# ControlBoard.net
KiCad netlist of a schematic drawn in EAGLE
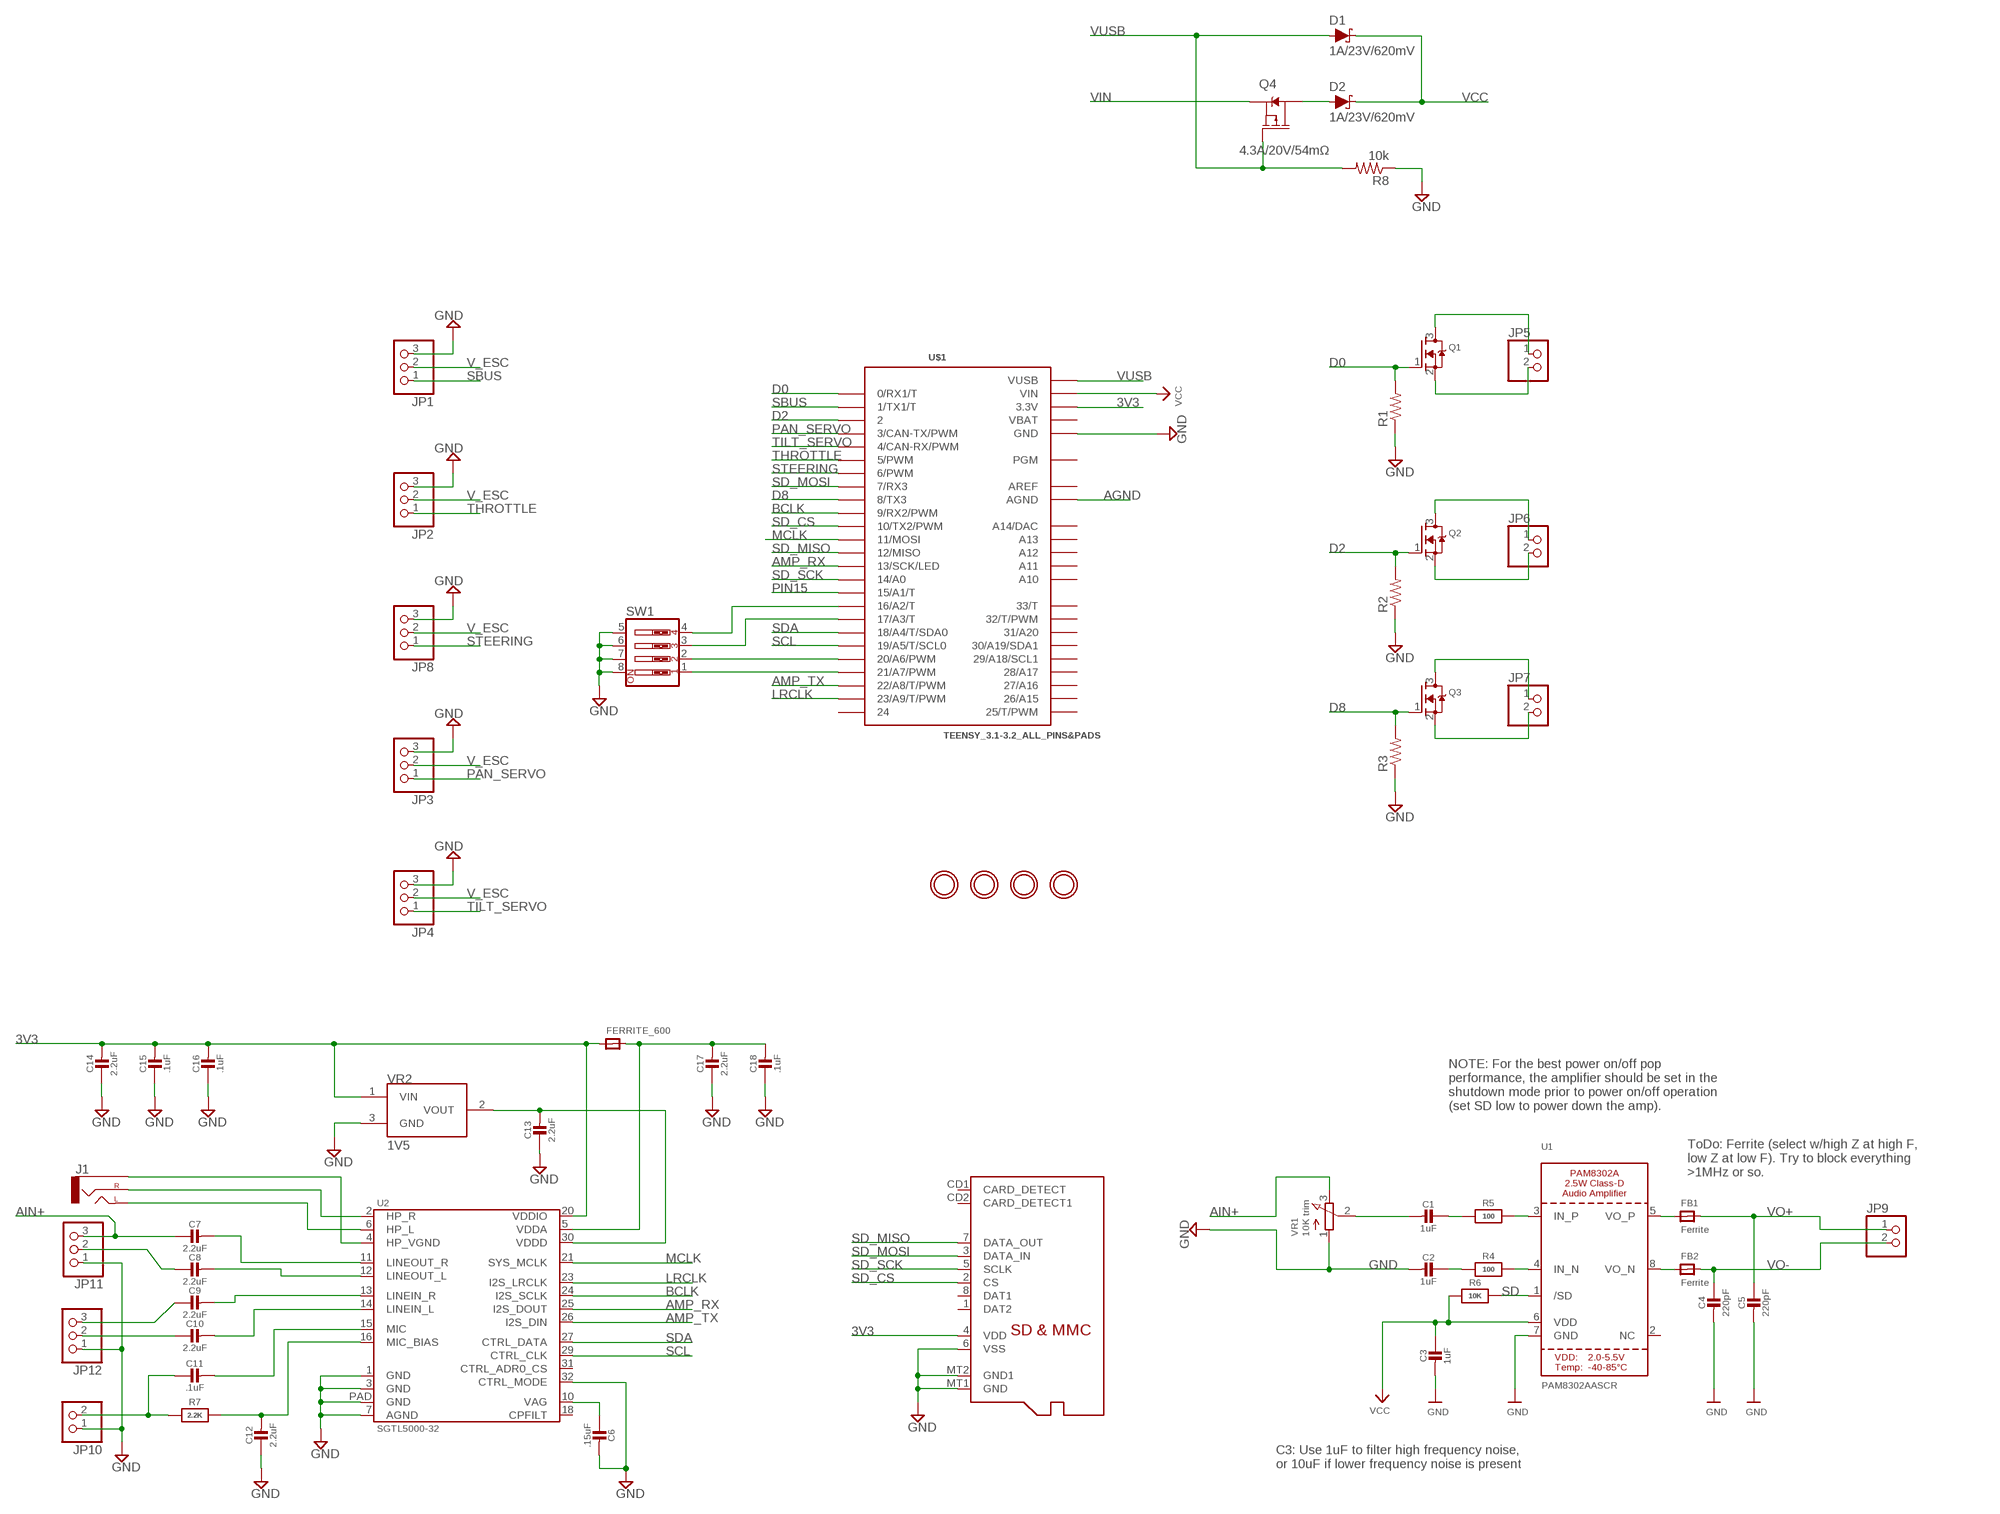
[diagram p0: schematic, sheet 1]

(export (version "E")
  (design (tool "Eeschema 10.0.6"))
  (components
    (comp (ref "C1")
      (value "1uF")
      (footprint "eagle-import:0805-NO")
      (libsource (lib "eagle-import") (part "microbuilder_CAP_CERAMIC0805-NOOUTLINE"))
    )
    (comp (ref "C2")
      (value "1uF")
      (footprint "eagle-import:0805-NO")
      (libsource (lib "eagle-import") (part "microbuilder_CAP_CERAMIC0805-NOOUTLINE"))
    )
    (comp (ref "C3")
      (value "1uF")
      (footprint "eagle-import:0805-NO")
      (libsource (lib "eagle-import") (part "microbuilder_CAP_CERAMIC0805-NOOUTLINE"))
    )
    (comp (ref "C4")
      (value "220pF")
      (footprint "eagle-import:0805-NO")
      (libsource (lib "eagle-import") (part "microbuilder_CAP_CERAMIC0805-NOOUTLINE"))
    )
    (comp (ref "C5")
      (value "220pF")
      (footprint "eagle-import:0805-NO")
      (libsource (lib "eagle-import") (part "microbuilder_CAP_CERAMIC0805-NOOUTLINE"))
    )
    (comp (ref "C6")
      (value ".15uF")
      (footprint "eagle-import:0805-NO")
      (libsource (lib "eagle-import") (part "microbuilder_CAP_CERAMIC0805-NOOUTLINE"))
    )
    (comp (ref "C7")
      (value "2.2uF")
      (footprint "eagle-import:0805-NO")
      (libsource (lib "eagle-import") (part "microbuilder_CAP_CERAMIC0805-NOOUTLINE"))
    )
    (comp (ref "C8")
      (value "2.2uF")
      (footprint "eagle-import:0805-NO")
      (libsource (lib "eagle-import") (part "microbuilder_CAP_CERAMIC0805-NOOUTLINE"))
    )
    (comp (ref "C9")
      (value "2.2uF")
      (footprint "eagle-import:0805-NO")
      (libsource (lib "eagle-import") (part "microbuilder_CAP_CERAMIC0805-NOOUTLINE"))
    )
    (comp (ref "C10")
      (value "2.2uF")
      (footprint "eagle-import:0805-NO")
      (libsource (lib "eagle-import") (part "microbuilder_CAP_CERAMIC0805-NOOUTLINE"))
    )
    (comp (ref "C11")
      (value ".1uF")
      (footprint "eagle-import:0805-NO")
      (libsource (lib "eagle-import") (part "microbuilder_CAP_CERAMIC0805-NOOUTLINE"))
    )
    (comp (ref "C12")
      (value "2.2uF")
      (footprint "eagle-import:0805-NO")
      (libsource (lib "eagle-import") (part "microbuilder_CAP_CERAMIC0805-NOOUTLINE"))
    )
    (comp (ref "C13")
      (value "2.2uF")
      (footprint "eagle-import:0805-NO")
      (libsource (lib "eagle-import") (part "CAP_CERAMIC0805-NOOUTLINE"))
    )
    (comp (ref "C14")
      (value "2.2uF")
      (footprint "eagle-import:0805-NO")
      (libsource (lib "eagle-import") (part "CAP_CERAMIC0805-NOOUTLINE"))
    )
    (comp (ref "C15")
      (value ".1uF")
      (footprint "eagle-import:0805-NO")
      (libsource (lib "eagle-import") (part "CAP_CERAMIC0805-NOOUTLINE"))
    )
    (comp (ref "C16")
      (value ".1uF")
      (footprint "eagle-import:0805-NO")
      (libsource (lib "eagle-import") (part "CAP_CERAMIC0805-NOOUTLINE"))
    )
    (comp (ref "C17")
      (value "2.2uF")
      (footprint "eagle-import:0805-NO")
      (libsource (lib "eagle-import") (part "CAP_CERAMIC0805-NOOUTLINE"))
    )
    (comp (ref "C18")
      (value ".1uF")
      (footprint "eagle-import:0805-NO")
      (libsource (lib "eagle-import") (part "CAP_CERAMIC0805-NOOUTLINE"))
    )
    (comp (ref "D1")
      (value "1A/23V/620mV")
      (footprint "eagle-import:SOD-323")
      (libsource (lib "eagle-import") (part "DIODE-SCHOTTKY-BAT20J"))
    )
    (comp (ref "D2")
      (value "1A/23V/620mV")
      (footprint "eagle-import:SOD-323")
      (libsource (lib "eagle-import") (part "DIODE-SCHOTTKY-BAT20J"))
    )
    (comp (ref "FB1")
      (value "Ferrite")
      (footprint "eagle-import:_0805")
      (libsource (lib "eagle-import") (part "microbuilder_FERRITE_0805"))
    )
    (comp (ref "FB2")
      (value "Ferrite")
      (footprint "eagle-import:_0805")
      (libsource (lib "eagle-import") (part "microbuilder_FERRITE_0805"))
    )
    (comp (ref "FERRITE_600")
      (value "FERRITE0805")
      (footprint "eagle-import:0805")
      (libsource (lib "eagle-import") (part "FERRITE0805"))
    )
    (comp (ref "J1")
      (value "AUDIO_JACK_2.5MM_2.5MM_SMD")
      (footprint "eagle-import:STEREOJACK2.5MM")
      (libsource (lib "eagle-import") (part "AUDIO_JACK_2.5MM_2.5MM_SMD"))
    )
    (comp (ref "JP1")
      (value "PINHD-1X3/90")
      (footprint "eagle-import:1X03_90")
      (libsource (lib "eagle-import") (part "PINHD-1X3/90"))
    )
    (comp (ref "JP2")
      (value "PINHD-1X3/90")
      (footprint "eagle-import:1X03_90")
      (libsource (lib "eagle-import") (part "PINHD-1X3/90"))
    )
    (comp (ref "JP3")
      (value "PINHD-1X3/90")
      (footprint "eagle-import:1X03_90")
      (libsource (lib "eagle-import") (part "PINHD-1X3/90"))
    )
    (comp (ref "JP4")
      (value "PINHD-1X3/90")
      (footprint "eagle-import:1X03_90")
      (libsource (lib "eagle-import") (part "PINHD-1X3/90"))
    )
    (comp (ref "JP5")
      (value "PINHD-1X2")
      (footprint "eagle-import:1X02")
      (libsource (lib "eagle-import") (part "PINHD-1X2"))
    )
    (comp (ref "JP6")
      (value "PINHD-1X2")
      (footprint "eagle-import:1X02")
      (libsource (lib "eagle-import") (part "PINHD-1X2"))
    )
    (comp (ref "JP7")
      (value "PINHD-1X2")
      (footprint "eagle-import:1X02")
      (libsource (lib "eagle-import") (part "PINHD-1X2"))
    )
    (comp (ref "JP8")
      (value "PINHD-1X3/90")
      (footprint "eagle-import:1X03_90")
      (libsource (lib "eagle-import") (part "PINHD-1X3/90"))
    )
    (comp (ref "JP9")
      (value "PINHD-1X2")
      (footprint "eagle-import:1X02")
      (libsource (lib "eagle-import") (part "PINHD-1X2"))
    )
    (comp (ref "JP10")
      (value "PINHD-1X2")
      (footprint "eagle-import:1X02")
      (libsource (lib "eagle-import") (part "PINHD-1X2"))
    )
    (comp (ref "JP11")
      (value "PINHD-1X3/90")
      (footprint "eagle-import:1X03_90")
      (libsource (lib "eagle-import") (part "PINHD-1X3/90"))
    )
    (comp (ref "JP12")
      (value "PINHD-1X3/90")
      (footprint "eagle-import:1X03_90")
      (libsource (lib "eagle-import") (part "PINHD-1X3/90"))
    )
    (comp (ref "Q1")
      (value "MOSFET-NREFLOW")
      (footprint "eagle-import:SOT23")
      (libsource (lib "eagle-import") (part "MOSFET-NREFLOW"))
    )
    (comp (ref "Q2")
      (value "MOSFET-NREFLOW")
      (footprint "eagle-import:SOT23")
      (libsource (lib "eagle-import") (part "MOSFET-NREFLOW"))
    )
    (comp (ref "Q3")
      (value "MOSFET-NREFLOW")
      (footprint "eagle-import:SOT23")
      (libsource (lib "eagle-import") (part "MOSFET-NREFLOW"))
    )
    (comp (ref "Q4")
      (value "4.3A/20V/54mΩ")
      (footprint "eagle-import:SOT23-3")
      (libsource (lib "eagle-import") (part "MOSFET_PCH-IRLML2244"))
    )
    (comp (ref "R1")
      (value "R-US_0207/7")
      (footprint "eagle-import:0207_7")
      (libsource (lib "eagle-import") (part "R-US_0207/7"))
    )
    (comp (ref "R2")
      (value "R-US_0207/7")
      (footprint "eagle-import:0207_7")
      (libsource (lib "eagle-import") (part "R-US_0207/7"))
    )
    (comp (ref "R3")
      (value "R-US_0207/7")
      (footprint "eagle-import:0207_7")
      (libsource (lib "eagle-import") (part "R-US_0207/7"))
    )
    (comp (ref "R4")
      (value "100")
      (footprint "eagle-import:0805-NO")
      (libsource (lib "eagle-import") (part "RESISTOR0805_NOOUTLINE"))
    )
    (comp (ref "R5")
      (value "100")
      (footprint "eagle-import:0805-NO")
      (libsource (lib "eagle-import") (part "RESISTOR0805_NOOUTLINE"))
    )
    (comp (ref "R6")
      (value "10K")
      (footprint "eagle-import:0805-NO")
      (libsource (lib "eagle-import") (part "RESISTOR0805_NOOUTLINE"))
    )
    (comp (ref "R7")
      (value "2.2K")
      (footprint "eagle-import:0805-NO")
      (libsource (lib "eagle-import") (part "RESISTOR0805_NOOUTLINE"))
    )
    (comp (ref "R8")
      (value "10k")
      (footprint "eagle-import:0207_7")
      (libsource (lib "eagle-import") (part "R-US_0207/7"))
    )
    (comp (ref "SW1")
      (value "SW_DIP-4")
      (footprint "eagle-import:EDG-04")
      (libsource (lib "eagle-import") (part "SW_DIP-4"))
    )
    (comp (ref "U$1")
      (value "TEENSY_3.1-3.2_ALL_PINS&PADS")
      (footprint "eagle-import:TEENSY_3.0-3.2_ALL_PINS_&_PADS")
      (libsource (lib "eagle-import") (part "TEENSY_3.1-3.2_ALL_PINS&PADS"))
    )
    (comp (ref "U$4")
      (value "MOUNTINGHOLE2.0")
      (footprint "eagle-import:MOUNTINGHOLE_2.0_PLATED")
      (libsource (lib "eagle-import") (part "MOUNTINGHOLE2.0"))
    )
    (comp (ref "U$5")
      (value "MOUNTINGHOLE2.0")
      (footprint "eagle-import:MOUNTINGHOLE_2.0_PLATED")
      (libsource (lib "eagle-import") (part "MOUNTINGHOLE2.0"))
    )
    (comp (ref "U$6")
      (value "MICROSD")
      (footprint "eagle-import:MICROSD")
      (libsource (lib "eagle-import") (part "MICROSD"))
    )
    (comp (ref "U$10")
      (value "MOUNTINGHOLE2.0")
      (footprint "eagle-import:MOUNTINGHOLE_2.0_PLATED")
      (libsource (lib "eagle-import") (part "MOUNTINGHOLE2.0"))
    )
    (comp (ref "U$11")
      (value "MOUNTINGHOLE2.0")
      (footprint "eagle-import:MOUNTINGHOLE_2.0_PLATED")
      (libsource (lib "eagle-import") (part "MOUNTINGHOLE2.0"))
    )
    (comp (ref "U1")
      (value "PAM8302AASCR")
      (footprint "eagle-import:MSOP8_0.65MM")
      (libsource (lib "eagle-import") (part "AUDIOAMP_PAM8302A"))
    )
    (comp (ref "U2")
      (value "SGTL5000-32")
      (footprint "eagle-import:QFN-32-5MM")
      (libsource (lib "eagle-import") (part "SGTL5000-32"))
    )
    (comp (ref "VR1")
      (value "10K trim")
      (footprint "eagle-import:TRIMPOT_BOURNS_3303W")
      (libsource (lib "eagle-import") (part "TRIMPOT3303W/X"))
    )
    (comp (ref "VR2")
      (value "1V5")
      (footprint "eagle-import:SOT23")
      (libsource (lib "eagle-import") (part "AP7313SOT"))
    )
  )
  (nets
    (net (code "1") (name "/3V3") (class "Default")
      (node (ref "C14") (pin "2") (pinfunction "2_2") (pintype "passive"))
      (node (ref "C15") (pin "2") (pinfunction "2_2") (pintype "passive"))
      (node (ref "C16") (pin "2") (pinfunction "2_2") (pintype "passive"))
      (node (ref "FERRITE_600") (pin "1") (pinfunction "P$1_1") (pintype "passive"))
      (node (ref "U$1") (pin "3.3V") (pinfunction "3.3V_3.3V") (pintype "power_in"))
      (node (ref "U$1") (pin "3.3V1") (pinfunction "3.3V_3.3V1") (pintype "power_in"))
      (node (ref "U$1") (pin "3.3V2") (pinfunction "3.3V_3.3V2") (pintype "power_in"))
      (node (ref "U$6") (pin "4") (pinfunction "VDD_4") (pintype "power_in"))
      (node (ref "U2") (pin "20") (pinfunction "VDDIO_20") (pintype "bidirectional"))
      (node (ref "VR2") (pin "1") (pinfunction "VIN_1") (pintype "power_in"))
    )
    (net (code "2") (name "/AGND") (class "Default")
      (node (ref "U$1") (pin "AGND") (pinfunction "AGND_AGND") (pintype "power_in"))
    )
    (net (code "3") (name "/AIN+") (class "Default")
      (node (ref "C7") (pin "1") (pinfunction "1_1") (pintype "passive"))
      (node (ref "JP11") (pin "3") (pinfunction "3_3") (pintype "passive"))
      (node (ref "VR1") (pin "3") (pinfunction "E_3") (pintype "passive"))
    )
    (net (code "4") (name "/AMP_RX") (class "Default")
      (node (ref "U$1") (pin "13") (pinfunction "13/SCK/LED_13") (pintype "bidirectional"))
      (node (ref "U2") (pin "25") (pinfunction "I2S_DOUT_25") (pintype "bidirectional"))
    )
    (net (code "5") (name "/AMP_TX") (class "Default")
      (node (ref "U$1") (pin "22/A8") (pinfunction "22/A8/T/PWM_22/A8") (pintype "bidirectional"))
      (node (ref "U2") (pin "26") (pinfunction "I2S_DIN_26") (pintype "bidirectional"))
    )
    (net (code "6") (name "/AREF") (class "Default")
      (node (ref "U$1") (pin "AREF") (pinfunction "AREF_AREF") (pintype "power_in"))
    )
    (net (code "7") (name "/BCLK") (class "Default")
      (node (ref "U$1") (pin "9") (pinfunction "9/RX2/PWM_9") (pintype "bidirectional"))
      (node (ref "U2") (pin "24") (pinfunction "I2S_SCLK_24") (pintype "bidirectional"))
    )
    (net (code "8") (name "/D0") (class "Default")
      (node (ref "Q1") (pin "1") (pinfunction "G_1") (pintype "bidirectional"))
      (node (ref "R1") (pin "2") (pinfunction "2_2") (pintype "passive"))
      (node (ref "U$1") (pin "0") (pinfunction "0/RX1/T_0") (pintype "bidirectional"))
    )
    (net (code "9") (name "/D2") (class "Default")
      (node (ref "Q2") (pin "1") (pinfunction "G_1") (pintype "bidirectional"))
      (node (ref "R2") (pin "2") (pinfunction "2_2") (pintype "passive"))
      (node (ref "U$1") (pin "2") (pinfunction "2_2") (pintype "bidirectional"))
    )
    (net (code "10") (name "/D8") (class "Default")
      (node (ref "Q3") (pin "1") (pinfunction "G_1") (pintype "bidirectional"))
      (node (ref "R3") (pin "2") (pinfunction "2_2") (pintype "passive"))
      (node (ref "U$1") (pin "8") (pinfunction "8/TX3_8") (pintype "bidirectional"))
    )
    (net (code "11") (name "/LRCLK") (class "Default")
      (node (ref "U$1") (pin "23/A9") (pinfunction "23/A9/T/PWM_23/A9") (pintype "bidirectional"))
      (node (ref "U2") (pin "23") (pinfunction "I2S_LRCLK_23") (pintype "bidirectional"))
    )
    (net (code "12") (name "/MCLK") (class "Default")
      (node (ref "U$1") (pin "11") (pinfunction "11/MOSI_11") (pintype "bidirectional"))
      (node (ref "U2") (pin "21") (pinfunction "SYS_MCLK_21") (pintype "bidirectional"))
    )
    (net (code "13") (name "/PAN_SERVO") (class "Default")
      (node (ref "JP3") (pin "1") (pinfunction "1_1") (pintype "passive"))
      (node (ref "U$1") (pin "3") (pinfunction "3/CAN-TX/PWM_3") (pintype "bidirectional"))
    )
    (net (code "14") (name "/PIN15") (class "Default")
      (node (ref "U$1") (pin "15/A1") (pinfunction "15/A1/T_15/A1") (pintype "bidirectional"))
    )
    (net (code "15") (name "/SBUS") (class "Default")
      (node (ref "JP1") (pin "1") (pinfunction "1_1") (pintype "passive"))
      (node (ref "U$1") (pin "1") (pinfunction "1/TX1/T_1") (pintype "bidirectional"))
    )
    (net (code "16") (name "/SCL") (class "Default")
      (node (ref "U$1") (pin "19/A5") (pinfunction "19/A5/T/SCL0_19/A5") (pintype "bidirectional"))
      (node (ref "U2") (pin "29") (pinfunction "CTRL_CLK_29") (pintype "bidirectional"))
    )
    (net (code "17") (name "/SD") (class "Default")
      (node (ref "R6") (pin "2") (pinfunction "2_2") (pintype "passive"))
      (node (ref "U1") (pin "1") (pinfunction "/SD_1") (pintype "input"))
    )
    (net (code "18") (name "/SDA") (class "Default")
      (node (ref "U$1") (pin "18/A4") (pinfunction "18/A4/T/SDA0_18/A4") (pintype "bidirectional"))
      (node (ref "U2") (pin "27") (pinfunction "CTRL_DATA_27") (pintype "bidirectional"))
    )
    (net (code "19") (name "/SD_CS") (class "Default")
      (node (ref "U$1") (pin "10") (pinfunction "10/TX2/PWM_10") (pintype "bidirectional"))
      (node (ref "U$6") (pin "2") (pinfunction "CS_2") (pintype "input"))
    )
    (net (code "20") (name "/SD_MISO") (class "Default")
      (node (ref "U$1") (pin "12") (pinfunction "12/MISO_12") (pintype "bidirectional"))
      (node (ref "U$6") (pin "7") (pinfunction "DATA_OUT_7") (pintype "output"))
    )
    (net (code "21") (name "/SD_MOSI") (class "Default")
      (node (ref "U$1") (pin "7") (pinfunction "7/RX3_7") (pintype "bidirectional"))
      (node (ref "U$6") (pin "3") (pinfunction "DATA_IN_3") (pintype "input"))
    )
    (net (code "22") (name "/SD_SCK") (class "Default")
      (node (ref "U$1") (pin "14/A0") (pinfunction "14/A0_14/A0") (pintype "bidirectional"))
      (node (ref "U$6") (pin "5") (pinfunction "SCLK_5") (pintype "input"))
    )
    (net (code "23") (name "/STEERING") (class "Default")
      (node (ref "JP8") (pin "1") (pinfunction "1_1") (pintype "passive"))
      (node (ref "U$1") (pin "6") (pinfunction "6/PWM_6") (pintype "bidirectional"))
    )
    (net (code "24") (name "/THROTTLE") (class "Default")
      (node (ref "JP2") (pin "1") (pinfunction "1_1") (pintype "passive"))
      (node (ref "U$1") (pin "5") (pinfunction "5/PWM_5") (pintype "bidirectional"))
    )
    (net (code "25") (name "/TILT_SERVO") (class "Default")
      (node (ref "JP4") (pin "1") (pinfunction "1_1") (pintype "passive"))
      (node (ref "U$1") (pin "4") (pinfunction "4/CAN-RX/PWM_4") (pintype "bidirectional"))
    )
    (net (code "26") (name "/VBAT") (class "Default")
      (node (ref "U$1") (pin "VBAT") (pinfunction "VBAT_VBAT") (pintype "power_in"))
    )
    (net (code "27") (name "/VIN") (class "Default")
      (node (ref "Q4") (pin "2") (pinfunction "S_2") (pintype "bidirectional"))
    )
    (net (code "28") (name "/VO+") (class "Default")
      (node (ref "C5") (pin "1") (pinfunction "1_1") (pintype "passive"))
      (node (ref "FB1") (pin "2") (pinfunction "P$2_2") (pintype "passive"))
      (node (ref "JP9") (pin "1") (pinfunction "1_1") (pintype "passive"))
    )
    (net (code "29") (name "/VO-") (class "Default")
      (node (ref "C4") (pin "1") (pinfunction "1_1") (pintype "passive"))
      (node (ref "FB2") (pin "2") (pinfunction "P$2_2") (pintype "passive"))
      (node (ref "JP9") (pin "2") (pinfunction "2_2") (pintype "passive"))
    )
    (net (code "30") (name "/VUSB") (class "Default")
      (node (ref "D1") (pin "A") (pinfunction "A_A") (pintype "passive"))
      (node (ref "Q4") (pin "1") (pinfunction "G_1") (pintype "bidirectional"))
      (node (ref "R8") (pin "2") (pinfunction "2_2") (pintype "passive"))
      (node (ref "U$1") (pin "VUSB") (pinfunction "VUSB_VUSB") (pintype "power_in"))
    )
    (net (code "31") (name "/V_ESC") (class "Default")
      (node (ref "JP1") (pin "2") (pinfunction "2_2") (pintype "passive"))
      (node (ref "JP2") (pin "2") (pinfunction "2_2") (pintype "passive"))
      (node (ref "JP3") (pin "2") (pinfunction "2_2") (pintype "passive"))
      (node (ref "JP4") (pin "2") (pinfunction "2_2") (pintype "passive"))
      (node (ref "JP8") (pin "2") (pinfunction "2_2") (pintype "passive"))
    )
    (net (code "32") (name "GND") (class "Default")
      (node (ref "C12") (pin "1") (pinfunction "1_1") (pintype "passive"))
      (node (ref "C13") (pin "1") (pinfunction "1_1") (pintype "passive"))
      (node (ref "C14") (pin "1") (pinfunction "1_1") (pintype "passive"))
      (node (ref "C15") (pin "1") (pinfunction "1_1") (pintype "passive"))
      (node (ref "C16") (pin "1") (pinfunction "1_1") (pintype "passive"))
      (node (ref "C17") (pin "1") (pinfunction "1_1") (pintype "passive"))
      (node (ref "C18") (pin "1") (pinfunction "1_1") (pintype "passive"))
      (node (ref "C2") (pin "2") (pinfunction "2_2") (pintype "passive"))
      (node (ref "C3") (pin "2") (pinfunction "2_2") (pintype "passive"))
      (node (ref "C4") (pin "2") (pinfunction "2_2") (pintype "passive"))
      (node (ref "C5") (pin "2") (pinfunction "2_2") (pintype "passive"))
      (node (ref "C6") (pin "2") (pinfunction "2_2") (pintype "passive"))
      (node (ref "JP1") (pin "3") (pinfunction "3_3") (pintype "passive"))
      (node (ref "JP10") (pin "1") (pinfunction "1_1") (pintype "passive"))
      (node (ref "JP11") (pin "1") (pinfunction "1_1") (pintype "passive"))
      (node (ref "JP12") (pin "1") (pinfunction "1_1") (pintype "passive"))
      (node (ref "JP2") (pin "3") (pinfunction "3_3") (pintype "passive"))
      (node (ref "JP3") (pin "3") (pinfunction "3_3") (pintype "passive"))
      (node (ref "JP4") (pin "3") (pinfunction "3_3") (pintype "passive"))
      (node (ref "JP8") (pin "3") (pinfunction "3_3") (pintype "passive"))
      (node (ref "R1") (pin "1") (pinfunction "1_1") (pintype "passive"))
      (node (ref "R2") (pin "1") (pinfunction "1_1") (pintype "passive"))
      (node (ref "R3") (pin "1") (pinfunction "1_1") (pintype "passive"))
      (node (ref "R8") (pin "1") (pinfunction "1_1") (pintype "passive"))
      (node (ref "SW1") (pin "5") (pinfunction "5_5") (pintype "passive"))
      (node (ref "SW1") (pin "6") (pinfunction "6_6") (pintype "passive"))
      (node (ref "SW1") (pin "7") (pinfunction "7_7") (pintype "passive"))
      (node (ref "SW1") (pin "8") (pinfunction "8_8") (pintype "passive"))
      (node (ref "U$1") (pin "GND") (pinfunction "GND_GND") (pintype "power_in"))
      (node (ref "U$1") (pin "GND1") (pinfunction "GND_GND1") (pintype "power_in"))
      (node (ref "U$1") (pin "GND2") (pinfunction "GND_GND2") (pintype "power_in"))
      (node (ref "U$6") (pin "6") (pinfunction "VSS_6") (pintype "power_in"))
      (node (ref "U$6") (pin "MT1") (pinfunction "GND_MT1") (pintype "power_in"))
      (node (ref "U$6") (pin "MT2") (pinfunction "GND1_MT2") (pintype "power_in"))
      (node (ref "U1") (pin "7") (pinfunction "GND_7") (pintype "power_in"))
      (node (ref "U2") (pin "1") (pinfunction "GND_1") (pintype "bidirectional"))
      (node (ref "U2") (pin "3") (pinfunction "GND_3") (pintype "bidirectional"))
      (node (ref "U2") (pin "32") (pinfunction "CTRL_MODE_32") (pintype "bidirectional"))
      (node (ref "U2") (pin "7") (pinfunction "AGND_7") (pintype "bidirectional"))
      (node (ref "U2") (pin "PAD") (pinfunction "GND_PAD") (pintype "bidirectional"))
      (node (ref "VR1") (pin "1") (pinfunction "A_1") (pintype "passive"))
      (node (ref "VR2") (pin "3") (pinfunction "GND_3") (pintype "power_in"))
    )
    (net (code "33") (name "Net-(C1-Pad1)") (class "Default")
      (node (ref "C1") (pin "1") (pinfunction "1_1") (pintype "passive"))
      (node (ref "R5") (pin "1") (pinfunction "1_1") (pintype "passive"))
    )
    (net (code "34") (name "Net-(C2-Pad1)") (class "Default")
      (node (ref "C2") (pin "1") (pinfunction "1_1") (pintype "passive"))
      (node (ref "R4") (pin "1") (pinfunction "1_1") (pintype "passive"))
    )
    (net (code "35") (name "Net-(C8-Pad1)") (class "Default")
      (node (ref "C8") (pin "1") (pinfunction "1_1") (pintype "passive"))
      (node (ref "JP11") (pin "2") (pinfunction "2_2") (pintype "passive"))
    )
    (net (code "36") (name "Net-(C9-Pad1)") (class "Default")
      (node (ref "C9") (pin "1") (pinfunction "1_1") (pintype "passive"))
      (node (ref "JP12") (pin "3") (pinfunction "3_3") (pintype "passive"))
    )
    (net (code "37") (name "Net-(C10-Pad1)") (class "Default")
      (node (ref "C10") (pin "1") (pinfunction "1_1") (pintype "passive"))
      (node (ref "JP12") (pin "2") (pinfunction "2_2") (pintype "passive"))
    )
    (net (code "38") (name "Net-(C11-Pad1)") (class "Default")
      (node (ref "C11") (pin "1") (pinfunction "1_1") (pintype "passive"))
      (node (ref "JP10") (pin "2") (pinfunction "2_2") (pintype "passive"))
      (node (ref "R7") (pin "1") (pinfunction "1_1") (pintype "passive"))
    )
    (net (code "39") (name "Net-(FB1-P$1)") (class "Default")
      (node (ref "FB1") (pin "1") (pinfunction "P$1_1") (pintype "passive"))
      (node (ref "U1") (pin "5") (pinfunction "VO_P_5") (pintype "output"))
    )
    (net (code "40") (name "Net-(FB2-P$1)") (class "Default")
      (node (ref "FB2") (pin "1") (pinfunction "P$1_1") (pintype "passive"))
      (node (ref "U1") (pin "8") (pinfunction "VO_N_8") (pintype "output"))
    )
    (net (code "41") (name "Net-(FERRITE_600-P$2)") (class "Default")
      (node (ref "C17") (pin "2") (pinfunction "2_2") (pintype "passive"))
      (node (ref "C18") (pin "2") (pinfunction "2_2") (pintype "passive"))
      (node (ref "FERRITE_600") (pin "2") (pinfunction "P$2_2") (pintype "passive"))
      (node (ref "U2") (pin "5") (pinfunction "VDDA_5") (pintype "bidirectional"))
    )
    (net (code "42") (name "Net-(J1-LEFT)") (class "Default")
      (node (ref "J1") (pin "1") (pinfunction "LEFT_1") (pintype "bidirectional"))
      (node (ref "U2") (pin "6") (pinfunction "HP_L_6") (pintype "bidirectional"))
    )
    (net (code "43") (name "Net-(J1-RIGHT)") (class "Default")
      (node (ref "J1") (pin "4") (pinfunction "RIGHT_4") (pintype "bidirectional"))
      (node (ref "U2") (pin "2") (pinfunction "HP_R_2") (pintype "bidirectional"))
    )
    (net (code "44") (name "Net-(J1-SLEEVE)") (class "Default")
      (node (ref "J1") (pin "5") (pinfunction "SLEEVE_5") (pintype "bidirectional"))
      (node (ref "U2") (pin "4") (pinfunction "HP_VGND_4") (pintype "bidirectional"))
    )
    (net (code "45") (name "Net-(Q1-D)") (class "Default")
      (node (ref "JP5") (pin "1") (pinfunction "1_1") (pintype "passive"))
      (node (ref "Q1") (pin "3") (pinfunction "D_3") (pintype "bidirectional"))
    )
    (net (code "46") (name "Net-(Q1-S)") (class "Default")
      (node (ref "JP5") (pin "2") (pinfunction "2_2") (pintype "passive"))
      (node (ref "Q1") (pin "2") (pinfunction "S_2") (pintype "bidirectional"))
    )
    (net (code "47") (name "Net-(Q2-D)") (class "Default")
      (node (ref "JP6") (pin "1") (pinfunction "1_1") (pintype "passive"))
      (node (ref "Q2") (pin "3") (pinfunction "D_3") (pintype "bidirectional"))
    )
    (net (code "48") (name "Net-(Q2-S)") (class "Default")
      (node (ref "JP6") (pin "2") (pinfunction "2_2") (pintype "passive"))
      (node (ref "Q2") (pin "2") (pinfunction "S_2") (pintype "bidirectional"))
    )
    (net (code "49") (name "Net-(Q3-D)") (class "Default")
      (node (ref "JP7") (pin "1") (pinfunction "1_1") (pintype "passive"))
      (node (ref "Q3") (pin "3") (pinfunction "D_3") (pintype "bidirectional"))
    )
    (net (code "50") (name "Net-(Q3-S)") (class "Default")
      (node (ref "JP7") (pin "2") (pinfunction "2_2") (pintype "passive"))
      (node (ref "Q3") (pin "2") (pinfunction "S_2") (pintype "bidirectional"))
    )
    (net (code "51") (name "Net-(Q4-D)") (class "Default")
      (node (ref "D2") (pin "A") (pinfunction "A_A") (pintype "passive"))
      (node (ref "Q4") (pin "3") (pinfunction "D_3") (pintype "bidirectional"))
    )
    (net (code "52") (name "Net-(U$1-16{slash}A2{slash}T)") (class "Default")
      (node (ref "SW1") (pin "4") (pinfunction "4_4") (pintype "passive"))
      (node (ref "U$1") (pin "16/A2") (pinfunction "16/A2/T_16/A2") (pintype "bidirectional"))
    )
    (net (code "53") (name "Net-(U$1-17{slash}A3{slash}T)") (class "Default")
      (node (ref "SW1") (pin "3") (pinfunction "3_3") (pintype "passive"))
      (node (ref "U$1") (pin "17/A3") (pinfunction "17/A3/T_17/A3") (pintype "bidirectional"))
    )
    (net (code "54") (name "Net-(U$1-20{slash}A6{slash}PWM)") (class "Default")
      (node (ref "SW1") (pin "2") (pinfunction "2_2") (pintype "passive"))
      (node (ref "U$1") (pin "20/A6") (pinfunction "20/A6/PWM_20/A6") (pintype "bidirectional"))
    )
    (net (code "55") (name "Net-(U$1-21{slash}A7{slash}PWM)") (class "Default")
      (node (ref "SW1") (pin "1") (pinfunction "1_1") (pintype "passive"))
      (node (ref "U$1") (pin "21/A7") (pinfunction "21/A7/PWM_21/A7") (pintype "bidirectional"))
    )
    (net (code "56") (name "Net-(U1-IN_N)") (class "Default")
      (node (ref "R4") (pin "2") (pinfunction "2_2") (pintype "passive"))
      (node (ref "U1") (pin "4") (pinfunction "IN_N_4") (pintype "input"))
    )
    (net (code "57") (name "Net-(U1-IN_P)") (class "Default")
      (node (ref "R5") (pin "2") (pinfunction "2_2") (pintype "passive"))
      (node (ref "U1") (pin "3") (pinfunction "IN_P_3") (pintype "input"))
    )
    (net (code "58") (name "Net-(U2-LINEIN_L)") (class "Default")
      (node (ref "C10") (pin "2") (pinfunction "2_2") (pintype "passive"))
      (node (ref "U2") (pin "14") (pinfunction "LINEIN_L_14") (pintype "bidirectional"))
    )
    (net (code "59") (name "Net-(U2-LINEIN_R)") (class "Default")
      (node (ref "C9") (pin "2") (pinfunction "2_2") (pintype "passive"))
      (node (ref "U2") (pin "13") (pinfunction "LINEIN_R_13") (pintype "bidirectional"))
    )
    (net (code "60") (name "Net-(U2-LINEOUT_L)") (class "Default")
      (node (ref "C8") (pin "2") (pinfunction "2_2") (pintype "passive"))
      (node (ref "U2") (pin "12") (pinfunction "LINEOUT_L_12") (pintype "bidirectional"))
    )
    (net (code "61") (name "Net-(U2-LINEOUT_R)") (class "Default")
      (node (ref "C7") (pin "2") (pinfunction "2_2") (pintype "passive"))
      (node (ref "U2") (pin "11") (pinfunction "LINEOUT_R_11") (pintype "bidirectional"))
    )
    (net (code "62") (name "Net-(U2-MIC)") (class "Default")
      (node (ref "C11") (pin "2") (pinfunction "2_2") (pintype "passive"))
      (node (ref "U2") (pin "15") (pinfunction "MIC_15") (pintype "bidirectional"))
    )
    (net (code "63") (name "Net-(U2-MIC_BIAS)") (class "Default")
      (node (ref "C12") (pin "2") (pinfunction "2_2") (pintype "passive"))
      (node (ref "R7") (pin "2") (pinfunction "2_2") (pintype "passive"))
      (node (ref "U2") (pin "16") (pinfunction "MIC_BIAS_16") (pintype "bidirectional"))
    )
    (net (code "64") (name "Net-(U2-VAG)") (class "Default")
      (node (ref "C6") (pin "1") (pinfunction "1_1") (pintype "passive"))
      (node (ref "U2") (pin "10") (pinfunction "VAG_10") (pintype "bidirectional"))
    )
    (net (code "65") (name "Net-(U2-VDDD)") (class "Default")
      (node (ref "C13") (pin "2") (pinfunction "2_2") (pintype "passive"))
      (node (ref "U2") (pin "30") (pinfunction "VDDD_30") (pintype "bidirectional"))
      (node (ref "VR2") (pin "2") (pinfunction "VOUT_2") (pintype "power_in"))
    )
    (net (code "66") (name "Net-(VR1-S)") (class "Default")
      (node (ref "C1") (pin "2") (pinfunction "2_2") (pintype "passive"))
      (node (ref "VR1") (pin "2") (pinfunction "S_2") (pintype "passive"))
    )
    (net (code "67") (name "VCC") (class "Default")
      (node (ref "C3") (pin "1") (pinfunction "1_1") (pintype "passive"))
      (node (ref "D1") (pin "C") (pinfunction "C_C") (pintype "passive"))
      (node (ref "D2") (pin "C") (pinfunction "C_C") (pintype "passive"))
      (node (ref "R6") (pin "1") (pinfunction "1_1") (pintype "passive"))
      (node (ref "U$1") (pin "VIN") (pinfunction "VIN_VIN") (pintype "power_in"))
      (node (ref "U1") (pin "6") (pinfunction "VDD_6") (pintype "power_in"))
    )
    (net (code "68") (name "unconnected-(U$1-25{slash}T{slash}PWM-Pad25)") (class "Default")
      (node (ref "U$1") (pin "25") (pinfunction "25/T/PWM_25") (pintype "bidirectional"))
    )
    (net (code "69") (name "unconnected-(U$1-26{slash}A15-Pad26)") (class "Default")
      (node (ref "U$1") (pin "26") (pinfunction "26/A15_26") (pintype "bidirectional"))
    )
    (net (code "70") (name "unconnected-(U$1-27{slash}A16-Pad27)") (class "Default")
      (node (ref "U$1") (pin "27") (pinfunction "27/A16_27") (pintype "bidirectional"))
    )
    (net (code "71") (name "unconnected-(U$1-28{slash}A17-Pad28)") (class "Default")
      (node (ref "U$1") (pin "28") (pinfunction "28/A17_28") (pintype "bidirectional"))
    )
    (net (code "72") (name "unconnected-(U$1-29{slash}A18{slash}SCL1-Pad29)") (class "Default")
      (node (ref "U$1") (pin "29") (pinfunction "29/A18/SCL1_29") (pintype "bidirectional"))
    )
    (net (code "73") (name "unconnected-(U$1-30{slash}A19{slash}SDA1-Pad30)") (class "Default")
      (node (ref "U$1") (pin "30") (pinfunction "30/A19/SDA1_30") (pintype "bidirectional"))
    )
    (net (code "74") (name "unconnected-(U$1-31{slash}A20-Pad31)") (class "Default")
      (node (ref "U$1") (pin "31") (pinfunction "31/A20_31") (pintype "bidirectional"))
    )
    (net (code "75") (name "unconnected-(U$1-32{slash}T{slash}PWM-Pad32)") (class "Default")
      (node (ref "U$1") (pin "32") (pinfunction "32/T/PWM_32") (pintype "bidirectional"))
    )
    (net (code "76") (name "unconnected-(U$1-33{slash}T-Pad33)") (class "Default")
      (node (ref "U$1") (pin "33") (pinfunction "33/T_33") (pintype "bidirectional"))
    )
    (net (code "77") (name "unconnected-(U$1-A14{slash}DAC-PadRESET{slash}DAC)") (class "Default")
      (node (ref "U$1") (pin "RESET/DAC") (pinfunction "A14/DAC_RESET/DAC") (pintype "bidirectional"))
    )
    (net (code "78") (name "unconnected-(U$1-Pad24)") (class "Default")
      (node (ref "U$1") (pin "24") (pinfunction "24_24") (pintype "bidirectional"))
    )
    (net (code "79") (name "unconnected-(U$1-PadA10)") (class "Default")
      (node (ref "U$1") (pin "A10") (pinfunction "A10_A10") (pintype "bidirectional"))
    )
    (net (code "80") (name "unconnected-(U$1-PadA11)") (class "Default")
      (node (ref "U$1") (pin "A11") (pinfunction "A11_A11") (pintype "bidirectional"))
    )
    (net (code "81") (name "unconnected-(U$1-PadA12)") (class "Default")
      (node (ref "U$1") (pin "A12") (pinfunction "A12_A12") (pintype "bidirectional"))
    )
    (net (code "82") (name "unconnected-(U$1-PadA13)") (class "Default")
      (node (ref "U$1") (pin "A13") (pinfunction "A13_A13") (pintype "bidirectional"))
    )
    (net (code "83") (name "unconnected-(U$1-PadPGM)") (class "Default")
      (node (ref "U$1") (pin "PGM") (pinfunction "PGM_PGM") (pintype "bidirectional"))
    )
    (net (code "84") (name "unconnected-(U$6-CARD_DETECT-PadCD1)") (class "Default")
      (node (ref "U$6") (pin "CD1") (pinfunction "CARD_DETECT_CD1") (pintype "passive"))
    )
    (net (code "85") (name "unconnected-(U$6-CARD_DETECT1-PadCD2)") (class "Default")
      (node (ref "U$6") (pin "CD2") (pinfunction "CARD_DETECT1_CD2") (pintype "passive"))
    )
    (net (code "86") (name "unconnected-(U$6-DAT1-Pad8)") (class "Default")
      (node (ref "U$6") (pin "8") (pinfunction "DAT1_8") (pintype "bidirectional"))
    )
    (net (code "87") (name "unconnected-(U$6-DAT2-Pad1)") (class "Default")
      (node (ref "U$6") (pin "1") (pinfunction "DAT2_1") (pintype "bidirectional"))
    )
    (net (code "88") (name "unconnected-(U1-NC-Pad2)") (class "Default")
      (node (ref "U1") (pin "2") (pinfunction "NC_2") (pintype "no_connect"))
    )
    (net (code "89") (name "unconnected-(U2-CPFILT-Pad18)") (class "Default")
      (node (ref "U2") (pin "18") (pinfunction "CPFILT_18") (pintype "bidirectional"))
    )
    (net (code "90") (name "unconnected-(U2-CTRL_ADR0_CS-Pad31)") (class "Default")
      (node (ref "U2") (pin "31") (pinfunction "CTRL_ADR0_CS_31") (pintype "bidirectional"))
    )
  )
)
